# Headstage_withFPGA.net
KiCad netlist of a schematic drawn in Altium Designer
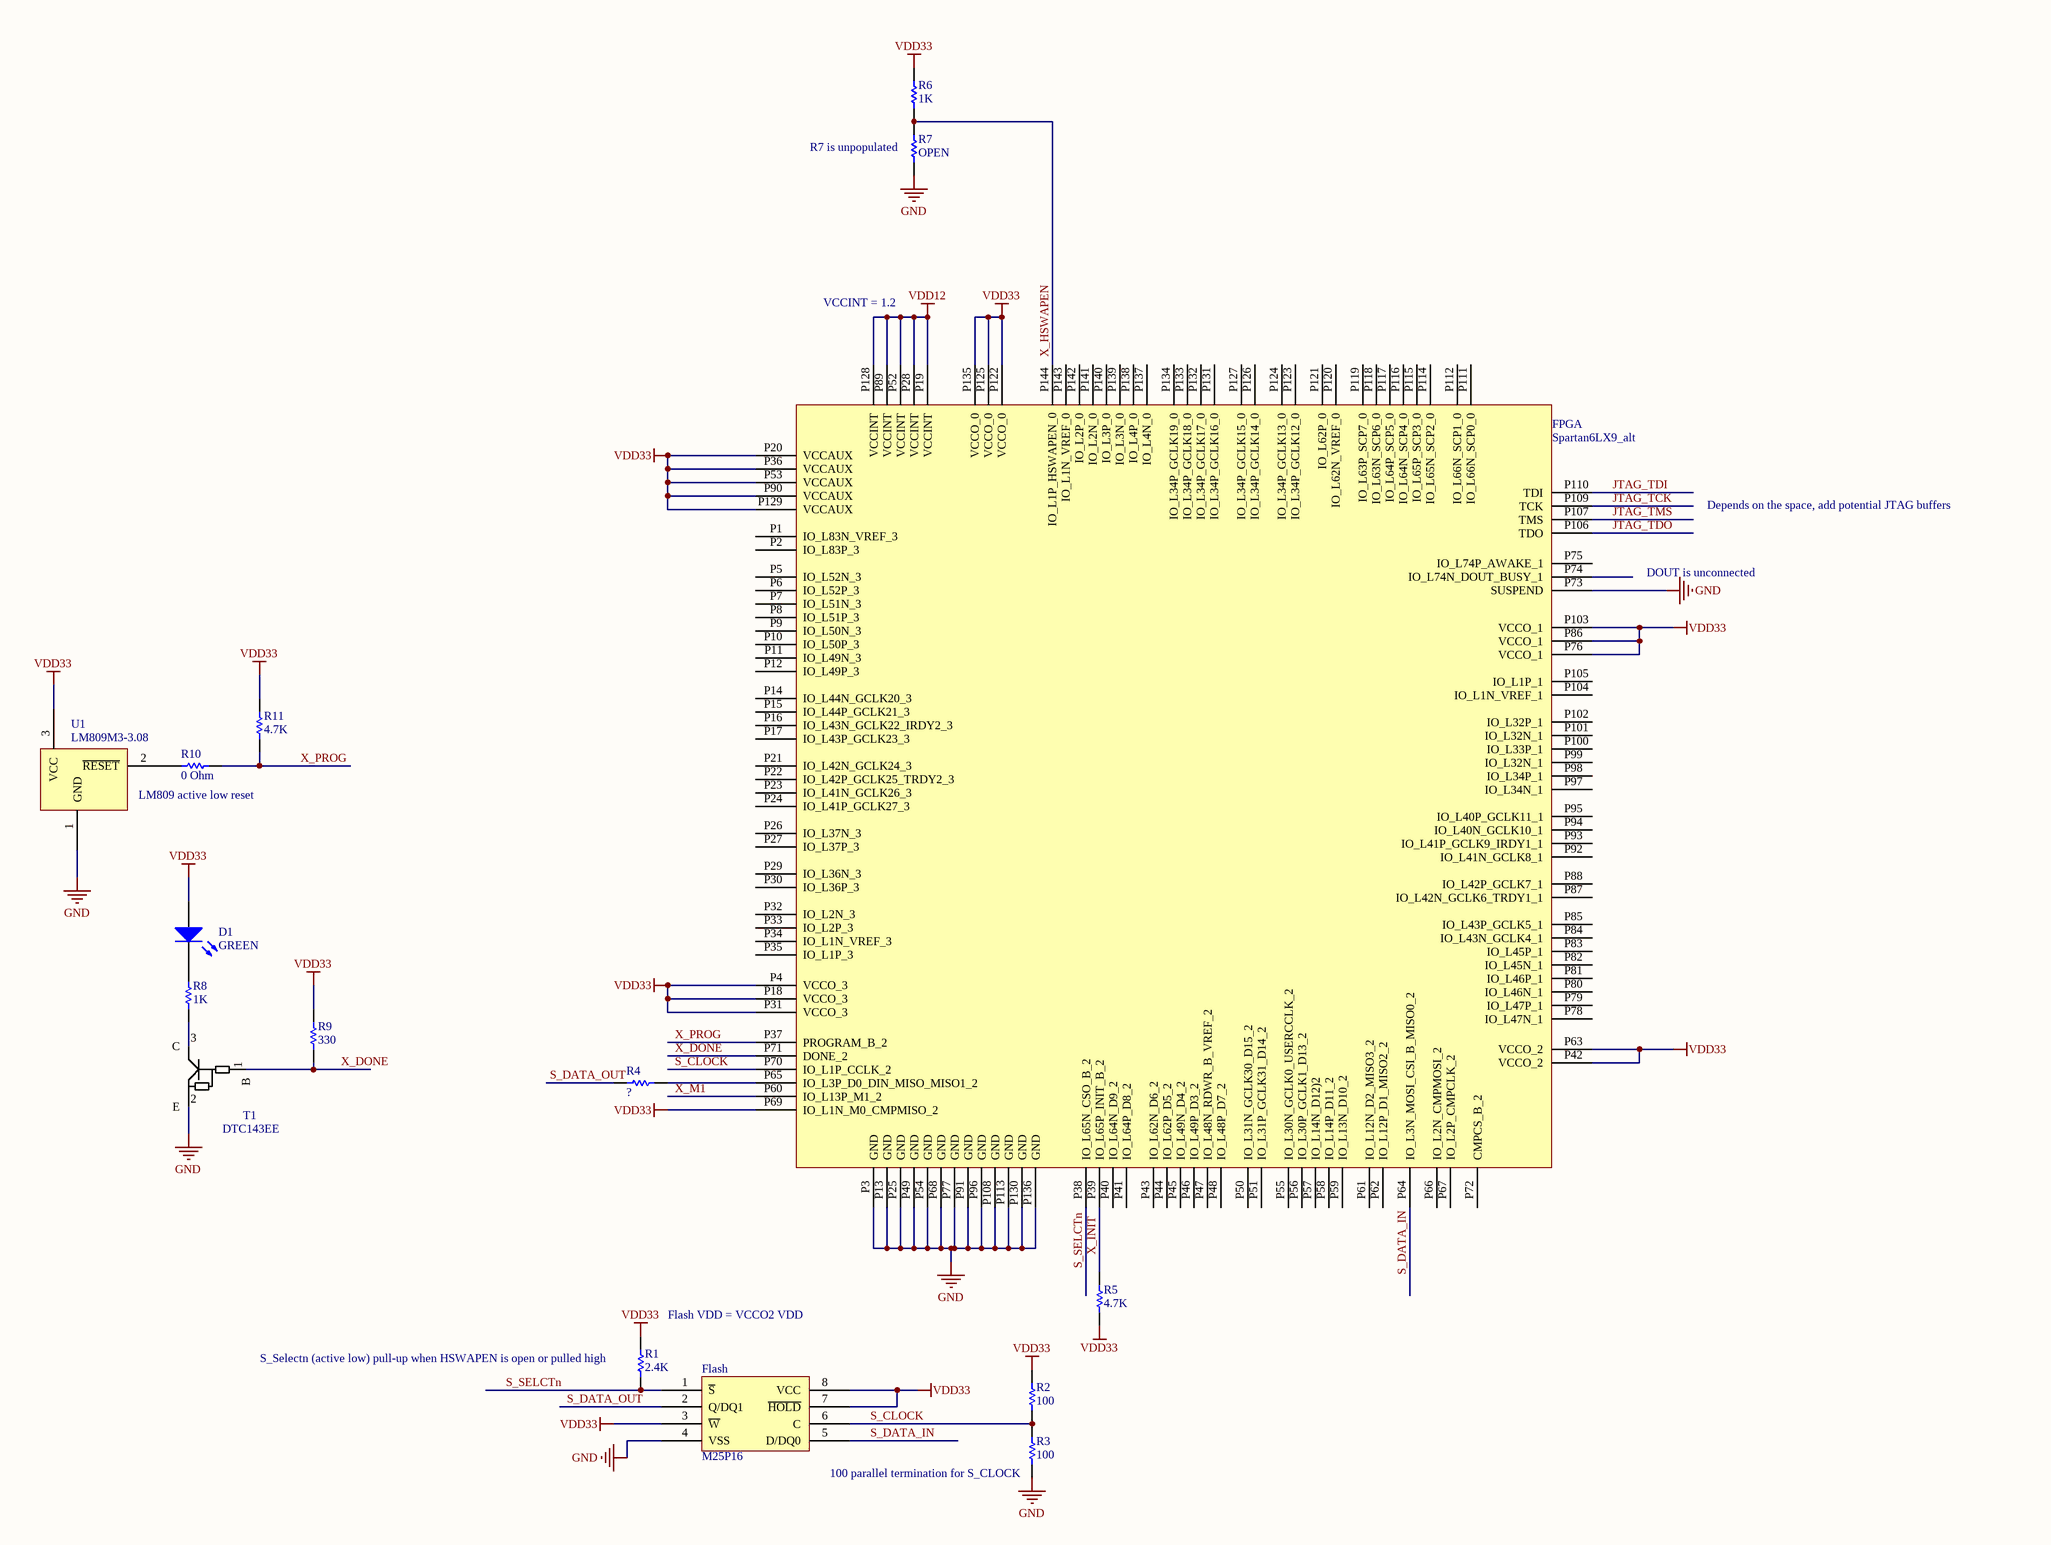
[diagram p0: Headstage_withFPGA.SchDoc]

(export (version "E")
  (design (tool "Eeschema 10.0.6"))
  (components
    (comp (ref "D1")
      (value "GREEN")
      (description "Typical BLUE SiC LED")
      (fields (field (name "PUBLISHER") "Altium Limited"))
      (libsource (lib "Miscellaneous Devices") (part "LED3"))
    )
    (comp (ref "Flash") (value "M25P16") (libsource (lib "Jack_SCH_Lib1") (part "M25P16")))
    (comp (ref "FPGA") (value "Spartan6LX9_alt") (libsource (lib "Jack_SCH_Lib1") (part "Spartan6LX9_alt")))
    (comp (ref "R1")
      (value "2.4K")
      (footprint "AXIAL-0.3")
      (description "Resistor")
      (fields (field (name "Comment") "Res1") (field (name "PUBLISHER") "Altium Limited"))
      (libsource (lib "Miscellaneous Devices") (part "Res1"))
    )
    (comp (ref "R2")
      (value "100")
      (footprint "AXIAL-0.3")
      (description "Resistor")
      (fields (field (name "Comment") "Res1") (field (name "PUBLISHER") "Altium Limited"))
      (libsource (lib "Miscellaneous Devices") (part "Res1"))
    )
    (comp (ref "R3")
      (value "100")
      (footprint "AXIAL-0.3")
      (description "Resistor")
      (fields (field (name "Comment") "Res1") (field (name "PUBLISHER") "Altium Limited"))
      (libsource (lib "Miscellaneous Devices") (part "Res1"))
    )
    (comp (ref "R4")
      (value "?")
      (footprint "AXIAL-0.3")
      (description "Resistor")
      (fields (field (name "Comment") "Res1") (field (name "PUBLISHER") "Altium Limited"))
      (libsource (lib "Miscellaneous Devices") (part "Res1"))
    )
    (comp (ref "R5")
      (value "4.7K")
      (footprint "AXIAL-0.3")
      (description "Resistor")
      (fields (field (name "Comment") "Res1") (field (name "PUBLISHER") "Altium Limited"))
      (libsource (lib "Miscellaneous Devices") (part "Res1"))
    )
    (comp (ref "R6")
      (value "1K")
      (footprint "AXIAL-0.3")
      (description "Resistor")
      (fields (field (name "Comment") "Res1") (field (name "PUBLISHER") "Altium Limited"))
      (libsource (lib "Miscellaneous Devices") (part "Res1"))
    )
    (comp (ref "R7")
      (value "OPEN")
      (footprint "AXIAL-0.3")
      (description "Resistor")
      (fields (field (name "Comment") "Res1") (field (name "PUBLISHER") "Altium Limited"))
      (libsource (lib "Miscellaneous Devices") (part "Res1"))
    )
    (comp (ref "R8")
      (value "1K")
      (footprint "AXIAL-0.3")
      (description "Resistor")
      (fields (field (name "Comment") "Res1") (field (name "PUBLISHER") "Altium Limited"))
      (libsource (lib "Miscellaneous Devices") (part "Res1"))
    )
    (comp (ref "R9")
      (value "330")
      (footprint "AXIAL-0.3")
      (description "Resistor")
      (fields (field (name "Comment") "Res1") (field (name "PUBLISHER") "Altium Limited"))
      (libsource (lib "Miscellaneous Devices") (part "Res1"))
    )
    (comp (ref "R10")
      (value "0 Ohm")
      (footprint "AXIAL-0.3")
      (description "Resistor")
      (fields (field (name "Comment") "Res1") (field (name "PUBLISHER") "Altium Limited"))
      (libsource (lib "Miscellaneous Devices") (part "Res1"))
    )
    (comp (ref "R11")
      (value "4.7K")
      (footprint "AXIAL-0.3")
      (description "Resistor")
      (fields (field (name "Comment") "Res1") (field (name "PUBLISHER") "Altium Limited"))
      (libsource (lib "Miscellaneous Devices") (part "Res1"))
    )
    (comp (ref "T1") (value "DTC143EE") (libsource (lib "Jack_SCH_Lib1") (part "DTC143EE")))
    (comp (ref "U1") (value "LM809M3-3.08") (libsource (lib "Jack_SCH_Lib1") (part "LM809M3-3.08")))
  )
  (nets
    (net (code "1") (name "/JTAG_TCK") (class "Default")
      (node (ref "FPGA") (pin "P109") (pinfunction "TCK_P109") (pintype "passive"))
    )
    (net (code "2") (name "/JTAG_TDI") (class "Default")
      (node (ref "FPGA") (pin "P110") (pinfunction "TDI_P110") (pintype "passive"))
    )
    (net (code "3") (name "/JTAG_TDO") (class "Default")
      (node (ref "FPGA") (pin "P106") (pinfunction "TDO_P106") (pintype "passive"))
    )
    (net (code "4") (name "/JTAG_TMS") (class "Default")
      (node (ref "FPGA") (pin "P107") (pinfunction "TMS_P107") (pintype "passive"))
    )
    (net (code "5") (name "/S_CLOCK") (class "Default")
      (node (ref "FPGA") (pin "P70") (pinfunction "IO_L1P_CCLK_2_P70") (pintype "passive"))
      (node (ref "Flash") (pin "6") (pinfunction "C_6") (pintype "passive"))
      (node (ref "R2") (pin "1") (pinfunction "1_1") (pintype "passive"))
      (node (ref "R3") (pin "2") (pinfunction "2_2") (pintype "passive"))
    )
    (net (code "6") (name "/S_DATA_IN") (class "Default")
      (node (ref "FPGA") (pin "P64") (pinfunction "IO_L3N_MOSI_CSI_B_MISO0_2_P64") (pintype "passive"))
      (node (ref "Flash") (pin "5") (pinfunction "D/DQ0_5") (pintype "passive"))
    )
    (net (code "7") (name "/S_DATA_OUT") (class "Default")
      (node (ref "Flash") (pin "2") (pinfunction "Q/DQ1_2") (pintype "passive"))
      (node (ref "R4") (pin "2") (pinfunction "2_2") (pintype "passive"))
    )
    (net (code "8") (name "/S_SELCTn") (class "Default")
      (node (ref "FPGA") (pin "P38") (pinfunction "IO_L65N_CSO_B_2_P38") (pintype "passive"))
      (node (ref "Flash") (pin "1") (pinfunction "~{S}_1") (pintype "passive"))
      (node (ref "R1") (pin "1") (pinfunction "1_1") (pintype "passive"))
    )
    (net (code "9") (name "/X_DONE") (class "Default")
      (node (ref "FPGA") (pin "P71") (pinfunction "DONE_2_P71") (pintype "passive"))
      (node (ref "R9") (pin "1") (pinfunction "1_1") (pintype "passive"))
      (node (ref "T1") (pin "1") (pinfunction "B_1") (pintype "passive"))
    )
    (net (code "10") (name "/X_HSWAPEN") (class "Default")
      (node (ref "FPGA") (pin "P144") (pinfunction "IO_L1P_HSWAPEN_0_P144") (pintype "passive"))
      (node (ref "R6") (pin "1") (pinfunction "1_1") (pintype "passive"))
      (node (ref "R7") (pin "2") (pinfunction "2_2") (pintype "passive"))
    )
    (net (code "11") (name "/X_INIT") (class "Default")
      (node (ref "FPGA") (pin "P39") (pinfunction "IO_L65P_INIT_B_2_P39") (pintype "passive"))
      (node (ref "R5") (pin "2") (pinfunction "2_2") (pintype "passive"))
    )
    (net (code "12") (name "/X_M1") (class "Default")
      (node (ref "FPGA") (pin "P60") (pinfunction "IO_L13P_M1_2_P60") (pintype "passive"))
    )
    (net (code "13") (name "/X_PROG") (class "Default")
      (node (ref "FPGA") (pin "P37") (pinfunction "PROGRAM_B_2_P37") (pintype "passive"))
      (node (ref "R10") (pin "1") (pinfunction "1_1") (pintype "passive"))
      (node (ref "R11") (pin "2") (pinfunction "2_2") (pintype "passive"))
    )
    (net (code "14") (name "GND") (class "Default")
      (node (ref "FPGA") (pin "P108") (pinfunction "GND_P108") (pintype "passive"))
      (node (ref "FPGA") (pin "P113") (pinfunction "GND_P113") (pintype "passive"))
      (node (ref "FPGA") (pin "P13") (pinfunction "GND_P13") (pintype "passive"))
      (node (ref "FPGA") (pin "P130") (pinfunction "GND_P130") (pintype "passive"))
      (node (ref "FPGA") (pin "P136") (pinfunction "GND_P136") (pintype "passive"))
      (node (ref "FPGA") (pin "P25") (pinfunction "GND_P25") (pintype "passive"))
      (node (ref "FPGA") (pin "P3") (pinfunction "GND_P3") (pintype "passive"))
      (node (ref "FPGA") (pin "P49") (pinfunction "GND_P49") (pintype "passive"))
      (node (ref "FPGA") (pin "P54") (pinfunction "GND_P54") (pintype "passive"))
      (node (ref "FPGA") (pin "P68") (pinfunction "GND_P68") (pintype "passive"))
      (node (ref "FPGA") (pin "P73") (pinfunction "SUSPEND_P73") (pintype "passive"))
      (node (ref "FPGA") (pin "P77") (pinfunction "GND_P77") (pintype "passive"))
      (node (ref "FPGA") (pin "P91") (pinfunction "GND_P91") (pintype "passive"))
      (node (ref "FPGA") (pin "P96") (pinfunction "GND_P96") (pintype "passive"))
      (node (ref "Flash") (pin "4") (pinfunction "VSS_4") (pintype "passive"))
      (node (ref "R3") (pin "1") (pinfunction "1_1") (pintype "passive"))
      (node (ref "R7") (pin "1") (pinfunction "1_1") (pintype "passive"))
      (node (ref "T1") (pin "2") (pinfunction "E_2") (pintype "passive"))
      (node (ref "U1") (pin "1") (pinfunction "GND_1") (pintype "passive"))
    )
    (net (code "15") (name "Net-(D1-K)") (class "Default")
      (node (ref "D1") (pin "2") (pinfunction "K_2") (pintype "passive"))
      (node (ref "R8") (pin "2") (pinfunction "2_2") (pintype "passive"))
    )
    (net (code "16") (name "Net-(FPGA-IO_L3P_D0_DIN_MISO_MISO1_2)") (class "Default")
      (node (ref "FPGA") (pin "P65") (pinfunction "IO_L3P_D0_DIN_MISO_MISO1_2_P65") (pintype "passive"))
      (node (ref "R4") (pin "1") (pinfunction "1_1") (pintype "passive"))
    )
    (net (code "17") (name "Net-(T1-C)") (class "Default")
      (node (ref "R8") (pin "1") (pinfunction "1_1") (pintype "passive"))
      (node (ref "T1") (pin "3") (pinfunction "C_3") (pintype "passive"))
    )
    (net (code "18") (name "Net-(U1-~{RESET})") (class "Default")
      (node (ref "R10") (pin "2") (pinfunction "2_2") (pintype "passive"))
      (node (ref "U1") (pin "2") (pinfunction "~{RESET}_2") (pintype "passive"))
    )
    (net (code "19") (name "VDD12") (class "Default")
      (node (ref "FPGA") (pin "P128") (pinfunction "VCCINT_P128") (pintype "passive"))
      (node (ref "FPGA") (pin "P19") (pinfunction "VCCINT_P19") (pintype "passive"))
      (node (ref "FPGA") (pin "P28") (pinfunction "VCCINT_P28") (pintype "passive"))
      (node (ref "FPGA") (pin "P52") (pinfunction "VCCINT_P52") (pintype "passive"))
      (node (ref "FPGA") (pin "P89") (pinfunction "VCCINT_P89") (pintype "passive"))
    )
    (net (code "20") (name "VDD33") (class "Default")
      (node (ref "D1") (pin "1") (pinfunction "A_1") (pintype "passive"))
      (node (ref "FPGA") (pin "P103") (pinfunction "VCCO_1_P103") (pintype "passive"))
      (node (ref "FPGA") (pin "P122") (pinfunction "VCCO_0_P122") (pintype "passive"))
      (node (ref "FPGA") (pin "P125") (pinfunction "VCCO_0_P125") (pintype "passive"))
      (node (ref "FPGA") (pin "P129") (pinfunction "VCCAUX_P129") (pintype "passive"))
      (node (ref "FPGA") (pin "P135") (pinfunction "VCCO_0_P135") (pintype "passive"))
      (node (ref "FPGA") (pin "P18") (pinfunction "VCCO_3_P18") (pintype "passive"))
      (node (ref "FPGA") (pin "P20") (pinfunction "VCCAUX_P20") (pintype "passive"))
      (node (ref "FPGA") (pin "P31") (pinfunction "VCCO_3_P31") (pintype "passive"))
      (node (ref "FPGA") (pin "P36") (pinfunction "VCCAUX_P36") (pintype "passive"))
      (node (ref "FPGA") (pin "P4") (pinfunction "VCCO_3_P4") (pintype "passive"))
      (node (ref "FPGA") (pin "P42") (pinfunction "VCCO_2_P42") (pintype "passive"))
      (node (ref "FPGA") (pin "P53") (pinfunction "VCCAUX_P53") (pintype "passive"))
      (node (ref "FPGA") (pin "P63") (pinfunction "VCCO_2_P63") (pintype "passive"))
      (node (ref "FPGA") (pin "P69") (pinfunction "IO_L1N_M0_CMPMISO_2_P69") (pintype "passive"))
      (node (ref "FPGA") (pin "P76") (pinfunction "VCCO_1_P76") (pintype "passive"))
      (node (ref "FPGA") (pin "P86") (pinfunction "VCCO_1_P86") (pintype "passive"))
      (node (ref "FPGA") (pin "P90") (pinfunction "VCCAUX_P90") (pintype "passive"))
      (node (ref "Flash") (pin "3") (pinfunction "~{W}_3") (pintype "passive"))
      (node (ref "Flash") (pin "7") (pinfunction "~{HOLD}_7") (pintype "passive"))
      (node (ref "Flash") (pin "8") (pinfunction "VCC_8") (pintype "passive"))
      (node (ref "R1") (pin "2") (pinfunction "2_2") (pintype "passive"))
      (node (ref "R11") (pin "1") (pinfunction "1_1") (pintype "passive"))
      (node (ref "R2") (pin "2") (pinfunction "2_2") (pintype "passive"))
      (node (ref "R5") (pin "1") (pinfunction "1_1") (pintype "passive"))
      (node (ref "R6") (pin "2") (pinfunction "2_2") (pintype "passive"))
      (node (ref "R9") (pin "2") (pinfunction "2_2") (pintype "passive"))
      (node (ref "U1") (pin "3") (pinfunction "VCC_3") (pintype "passive"))
    )
    (net (code "21") (name "unconnected-(FPGA-CMPCS_B_2-PadP72)") (class "Default")
      (node (ref "FPGA") (pin "P72") (pinfunction "CMPCS_B_2_P72") (pintype "passive"))
    )
    (net (code "22") (name "unconnected-(FPGA-IO_L1N_VREF_0-PadP143)") (class "Default")
      (node (ref "FPGA") (pin "P143") (pinfunction "IO_L1N_VREF_0_P143") (pintype "passive"))
    )
    (net (code "23") (name "unconnected-(FPGA-IO_L1N_VREF_1-PadP104)") (class "Default")
      (node (ref "FPGA") (pin "P104") (pinfunction "IO_L1N_VREF_1_P104") (pintype "passive"))
    )
    (net (code "24") (name "unconnected-(FPGA-IO_L1N_VREF_3-PadP34)") (class "Default")
      (node (ref "FPGA") (pin "P34") (pinfunction "IO_L1N_VREF_3_P34") (pintype "passive"))
    )
    (net (code "25") (name "unconnected-(FPGA-IO_L1P_1-PadP105)") (class "Default")
      (node (ref "FPGA") (pin "P105") (pinfunction "IO_L1P_1_P105") (pintype "passive"))
    )
    (net (code "26") (name "unconnected-(FPGA-IO_L1P_3-PadP35)") (class "Default")
      (node (ref "FPGA") (pin "P35") (pinfunction "IO_L1P_3_P35") (pintype "passive"))
    )
    (net (code "27") (name "unconnected-(FPGA-IO_L2N_0-PadP141)") (class "Default")
      (node (ref "FPGA") (pin "P141") (pinfunction "IO_L2N_0_P141") (pintype "passive"))
    )
    (net (code "28") (name "unconnected-(FPGA-IO_L2N_3-PadP32)") (class "Default")
      (node (ref "FPGA") (pin "P32") (pinfunction "IO_L2N_3_P32") (pintype "passive"))
    )
    (net (code "29") (name "unconnected-(FPGA-IO_L2N_CMPMOSI_2-PadP66)") (class "Default")
      (node (ref "FPGA") (pin "P66") (pinfunction "IO_L2N_CMPMOSI_2_P66") (pintype "passive"))
    )
    (net (code "30") (name "unconnected-(FPGA-IO_L2P_0-PadP142)") (class "Default")
      (node (ref "FPGA") (pin "P142") (pinfunction "IO_L2P_0_P142") (pintype "passive"))
    )
    (net (code "31") (name "unconnected-(FPGA-IO_L2P_3-PadP33)") (class "Default")
      (node (ref "FPGA") (pin "P33") (pinfunction "IO_L2P_3_P33") (pintype "passive"))
    )
    (net (code "32") (name "unconnected-(FPGA-IO_L2P_CMPCLK_2-PadP67)") (class "Default")
      (node (ref "FPGA") (pin "P67") (pinfunction "IO_L2P_CMPCLK_2_P67") (pintype "passive"))
    )
    (net (code "33") (name "unconnected-(FPGA-IO_L3N_0-PadP139)") (class "Default")
      (node (ref "FPGA") (pin "P139") (pinfunction "IO_L3N_0_P139") (pintype "passive"))
    )
    (net (code "34") (name "unconnected-(FPGA-IO_L3P_0-PadP140)") (class "Default")
      (node (ref "FPGA") (pin "P140") (pinfunction "IO_L3P_0_P140") (pintype "passive"))
    )
    (net (code "35") (name "unconnected-(FPGA-IO_L4N_0-PadP137)") (class "Default")
      (node (ref "FPGA") (pin "P137") (pinfunction "IO_L4N_0_P137") (pintype "passive"))
    )
    (net (code "36") (name "unconnected-(FPGA-IO_L4P_0-PadP138)") (class "Default")
      (node (ref "FPGA") (pin "P138") (pinfunction "IO_L4P_0_P138") (pintype "passive"))
    )
    (net (code "37") (name "unconnected-(FPGA-IO_L12N_D2_MISO3_2-PadP61)") (class "Default")
      (node (ref "FPGA") (pin "P61") (pinfunction "IO_L12N_D2_MISO3_2_P61") (pintype "passive"))
    )
    (net (code "38") (name "unconnected-(FPGA-IO_L12P_D1_MISO2_2-PadP62)") (class "Default")
      (node (ref "FPGA") (pin "P62") (pinfunction "IO_L12P_D1_MISO2_2_P62") (pintype "passive"))
    )
    (net (code "39") (name "unconnected-(FPGA-IO_L13N_D10_2-PadP59)") (class "Default")
      (node (ref "FPGA") (pin "P59") (pinfunction "IO_L13N_D10_2_P59") (pintype "passive"))
    )
    (net (code "40") (name "unconnected-(FPGA-IO_L14N_D12)2-PadP57)") (class "Default")
      (node (ref "FPGA") (pin "P57") (pinfunction "IO_L14N_D12)2_P57") (pintype "passive"))
    )
    (net (code "41") (name "unconnected-(FPGA-IO_L14P_D11_2-PadP58)") (class "Default")
      (node (ref "FPGA") (pin "P58") (pinfunction "IO_L14P_D11_2_P58") (pintype "passive"))
    )
    (net (code "42") (name "unconnected-(FPGA-IO_L30N_GCLK0_USERCCLK_2-PadP55)") (class "Default")
      (node (ref "FPGA") (pin "P55") (pinfunction "IO_L30N_GCLK0_USERCCLK_2_P55") (pintype "passive"))
    )
    (net (code "43") (name "unconnected-(FPGA-IO_L30P_GCLK1_D13_2-PadP56)") (class "Default")
      (node (ref "FPGA") (pin "P56") (pinfunction "IO_L30P_GCLK1_D13_2_P56") (pintype "passive"))
    )
    (net (code "44") (name "unconnected-(FPGA-IO_L31N_GCLK30_D15_2-PadP50)") (class "Default")
      (node (ref "FPGA") (pin "P50") (pinfunction "IO_L31N_GCLK30_D15_2_P50") (pintype "passive"))
    )
    (net (code "45") (name "unconnected-(FPGA-IO_L31P_GCLK31_D14_2-PadP51)") (class "Default")
      (node (ref "FPGA") (pin "P51") (pinfunction "IO_L31P_GCLK31_D14_2_P51") (pintype "passive"))
    )
    (net (code "46") (name "unconnected-(FPGA-IO_L32N_1-PadP99)") (class "Default")
      (node (ref "FPGA") (pin "P99") (pinfunction "IO_L32N_1_P99") (pintype "passive"))
    )
    (net (code "47") (name "unconnected-(FPGA-IO_L32N_1-PadP101)") (class "Default")
      (node (ref "FPGA") (pin "P101") (pinfunction "IO_L32N_1_P101") (pintype "passive"))
    )
    (net (code "48") (name "unconnected-(FPGA-IO_L32P_1-PadP102)") (class "Default")
      (node (ref "FPGA") (pin "P102") (pinfunction "IO_L32P_1_P102") (pintype "passive"))
    )
    (net (code "49") (name "unconnected-(FPGA-IO_L33P_1-PadP100)") (class "Default")
      (node (ref "FPGA") (pin "P100") (pinfunction "IO_L33P_1_P100") (pintype "passive"))
    )
    (net (code "50") (name "unconnected-(FPGA-IO_L34N_1-PadP97)") (class "Default")
      (node (ref "FPGA") (pin "P97") (pinfunction "IO_L34N_1_P97") (pintype "passive"))
    )
    (net (code "51") (name "unconnected-(FPGA-IO_L34P_1-PadP98)") (class "Default")
      (node (ref "FPGA") (pin "P98") (pinfunction "IO_L34P_1_P98") (pintype "passive"))
    )
    (net (code "52") (name "unconnected-(FPGA-IO_L34P_GCLK12_0-PadP123)") (class "Default")
      (node (ref "FPGA") (pin "P123") (pinfunction "IO_L34P_GCLK12_0_P123") (pintype "passive"))
    )
    (net (code "53") (name "unconnected-(FPGA-IO_L34P_GCLK13_0-PadP124)") (class "Default")
      (node (ref "FPGA") (pin "P124") (pinfunction "IO_L34P_GCLK13_0_P124") (pintype "passive"))
    )
    (net (code "54") (name "unconnected-(FPGA-IO_L34P_GCLK14_0-PadP126)") (class "Default")
      (node (ref "FPGA") (pin "P126") (pinfunction "IO_L34P_GCLK14_0_P126") (pintype "passive"))
    )
    (net (code "55") (name "unconnected-(FPGA-IO_L34P_GCLK15_0-PadP127)") (class "Default")
      (node (ref "FPGA") (pin "P127") (pinfunction "IO_L34P_GCLK15_0_P127") (pintype "passive"))
    )
    (net (code "56") (name "unconnected-(FPGA-IO_L34P_GCLK16_0-PadP131)") (class "Default")
      (node (ref "FPGA") (pin "P131") (pinfunction "IO_L34P_GCLK16_0_P131") (pintype "passive"))
    )
    (net (code "57") (name "unconnected-(FPGA-IO_L34P_GCLK17_0-PadP132)") (class "Default")
      (node (ref "FPGA") (pin "P132") (pinfunction "IO_L34P_GCLK17_0_P132") (pintype "passive"))
    )
    (net (code "58") (name "unconnected-(FPGA-IO_L34P_GCLK18_0-PadP133)") (class "Default")
      (node (ref "FPGA") (pin "P133") (pinfunction "IO_L34P_GCLK18_0_P133") (pintype "passive"))
    )
    (net (code "59") (name "unconnected-(FPGA-IO_L34P_GCLK19_0-PadP134)") (class "Default")
      (node (ref "FPGA") (pin "P134") (pinfunction "IO_L34P_GCLK19_0_P134") (pintype "passive"))
    )
    (net (code "60") (name "unconnected-(FPGA-IO_L36N_3-PadP29)") (class "Default")
      (node (ref "FPGA") (pin "P29") (pinfunction "IO_L36N_3_P29") (pintype "passive"))
    )
    (net (code "61") (name "unconnected-(FPGA-IO_L36P_3-PadP30)") (class "Default")
      (node (ref "FPGA") (pin "P30") (pinfunction "IO_L36P_3_P30") (pintype "passive"))
    )
    (net (code "62") (name "unconnected-(FPGA-IO_L37N_3-PadP26)") (class "Default")
      (node (ref "FPGA") (pin "P26") (pinfunction "IO_L37N_3_P26") (pintype "passive"))
    )
    (net (code "63") (name "unconnected-(FPGA-IO_L37P_3-PadP27)") (class "Default")
      (node (ref "FPGA") (pin "P27") (pinfunction "IO_L37P_3_P27") (pintype "passive"))
    )
    (net (code "64") (name "unconnected-(FPGA-IO_L40N_GCLK10_1-PadP94)") (class "Default")
      (node (ref "FPGA") (pin "P94") (pinfunction "IO_L40N_GCLK10_1_P94") (pintype "passive"))
    )
    (net (code "65") (name "unconnected-(FPGA-IO_L40P_GCLK11_1-PadP95)") (class "Default")
      (node (ref "FPGA") (pin "P95") (pinfunction "IO_L40P_GCLK11_1_P95") (pintype "passive"))
    )
    (net (code "66") (name "unconnected-(FPGA-IO_L41N_GCLK8_1-PadP92)") (class "Default")
      (node (ref "FPGA") (pin "P92") (pinfunction "IO_L41N_GCLK8_1_P92") (pintype "passive"))
    )
    (net (code "67") (name "unconnected-(FPGA-IO_L41N_GCLK26_3-PadP23)") (class "Default")
      (node (ref "FPGA") (pin "P23") (pinfunction "IO_L41N_GCLK26_3_P23") (pintype "passive"))
    )
    (net (code "68") (name "unconnected-(FPGA-IO_L41P_GCLK9_IRDY1_1-PadP93)") (class "Default")
      (node (ref "FPGA") (pin "P93") (pinfunction "IO_L41P_GCLK9_IRDY1_1_P93") (pintype "passive"))
    )
    (net (code "69") (name "unconnected-(FPGA-IO_L41P_GCLK27_3-PadP24)") (class "Default")
      (node (ref "FPGA") (pin "P24") (pinfunction "IO_L41P_GCLK27_3_P24") (pintype "passive"))
    )
    (net (code "70") (name "unconnected-(FPGA-IO_L42N_GCLK6_TRDY1_1-PadP87)") (class "Default")
      (node (ref "FPGA") (pin "P87") (pinfunction "IO_L42N_GCLK6_TRDY1_1_P87") (pintype "passive"))
    )
    (net (code "71") (name "unconnected-(FPGA-IO_L42N_GCLK24_3-PadP21)") (class "Default")
      (node (ref "FPGA") (pin "P21") (pinfunction "IO_L42N_GCLK24_3_P21") (pintype "passive"))
    )
    (net (code "72") (name "unconnected-(FPGA-IO_L42P_GCLK7_1-PadP88)") (class "Default")
      (node (ref "FPGA") (pin "P88") (pinfunction "IO_L42P_GCLK7_1_P88") (pintype "passive"))
    )
    (net (code "73") (name "unconnected-(FPGA-IO_L42P_GCLK25_TRDY2_3-PadP22)") (class "Default")
      (node (ref "FPGA") (pin "P22") (pinfunction "IO_L42P_GCLK25_TRDY2_3_P22") (pintype "passive"))
    )
    (net (code "74") (name "unconnected-(FPGA-IO_L43N_GCLK4_1-PadP84)") (class "Default")
      (node (ref "FPGA") (pin "P84") (pinfunction "IO_L43N_GCLK4_1_P84") (pintype "passive"))
    )
    (net (code "75") (name "unconnected-(FPGA-IO_L43N_GCLK22_IRDY2_3-PadP16)") (class "Default")
      (node (ref "FPGA") (pin "P16") (pinfunction "IO_L43N_GCLK22_IRDY2_3_P16") (pintype "passive"))
    )
    (net (code "76") (name "unconnected-(FPGA-IO_L43P_GCLK5_1-PadP85)") (class "Default")
      (node (ref "FPGA") (pin "P85") (pinfunction "IO_L43P_GCLK5_1_P85") (pintype "passive"))
    )
    (net (code "77") (name "unconnected-(FPGA-IO_L43P_GCLK23_3-PadP17)") (class "Default")
      (node (ref "FPGA") (pin "P17") (pinfunction "IO_L43P_GCLK23_3_P17") (pintype "passive"))
    )
    (net (code "78") (name "unconnected-(FPGA-IO_L44N_GCLK20_3-PadP14)") (class "Default")
      (node (ref "FPGA") (pin "P14") (pinfunction "IO_L44N_GCLK20_3_P14") (pintype "passive"))
    )
    (net (code "79") (name "unconnected-(FPGA-IO_L44P_GCLK21_3-PadP15)") (class "Default")
      (node (ref "FPGA") (pin "P15") (pinfunction "IO_L44P_GCLK21_3_P15") (pintype "passive"))
    )
    (net (code "80") (name "unconnected-(FPGA-IO_L45N_1-PadP82)") (class "Default")
      (node (ref "FPGA") (pin "P82") (pinfunction "IO_L45N_1_P82") (pintype "passive"))
    )
    (net (code "81") (name "unconnected-(FPGA-IO_L45P_1-PadP83)") (class "Default")
      (node (ref "FPGA") (pin "P83") (pinfunction "IO_L45P_1_P83") (pintype "passive"))
    )
    (net (code "82") (name "unconnected-(FPGA-IO_L46N_1-PadP80)") (class "Default")
      (node (ref "FPGA") (pin "P80") (pinfunction "IO_L46N_1_P80") (pintype "passive"))
    )
    (net (code "83") (name "unconnected-(FPGA-IO_L46P_1-PadP81)") (class "Default")
      (node (ref "FPGA") (pin "P81") (pinfunction "IO_L46P_1_P81") (pintype "passive"))
    )
    (net (code "84") (name "unconnected-(FPGA-IO_L47N_1-PadP78)") (class "Default")
      (node (ref "FPGA") (pin "P78") (pinfunction "IO_L47N_1_P78") (pintype "passive"))
    )
    (net (code "85") (name "unconnected-(FPGA-IO_L47P_1-PadP79)") (class "Default")
      (node (ref "FPGA") (pin "P79") (pinfunction "IO_L47P_1_P79") (pintype "passive"))
    )
    (net (code "86") (name "unconnected-(FPGA-IO_L48N_RDWR_B_VREF_2-PadP47)") (class "Default")
      (node (ref "FPGA") (pin "P47") (pinfunction "IO_L48N_RDWR_B_VREF_2_P47") (pintype "passive"))
    )
    (net (code "87") (name "unconnected-(FPGA-IO_L48P_D7_2-PadP48)") (class "Default")
      (node (ref "FPGA") (pin "P48") (pinfunction "IO_L48P_D7_2_P48") (pintype "passive"))
    )
    (net (code "88") (name "unconnected-(FPGA-IO_L49N_3-PadP11)") (class "Default")
      (node (ref "FPGA") (pin "P11") (pinfunction "IO_L49N_3_P11") (pintype "passive"))
    )
    (net (code "89") (name "unconnected-(FPGA-IO_L49N_D4_2-PadP45)") (class "Default")
      (node (ref "FPGA") (pin "P45") (pinfunction "IO_L49N_D4_2_P45") (pintype "passive"))
    )
    (net (code "90") (name "unconnected-(FPGA-IO_L49P_3-PadP12)") (class "Default")
      (node (ref "FPGA") (pin "P12") (pinfunction "IO_L49P_3_P12") (pintype "passive"))
    )
    (net (code "91") (name "unconnected-(FPGA-IO_L49P_D3_2-PadP46)") (class "Default")
      (node (ref "FPGA") (pin "P46") (pinfunction "IO_L49P_D3_2_P46") (pintype "passive"))
    )
    (net (code "92") (name "unconnected-(FPGA-IO_L50N_3-PadP9)") (class "Default")
      (node (ref "FPGA") (pin "P9") (pinfunction "IO_L50N_3_P9") (pintype "passive"))
    )
    (net (code "93") (name "unconnected-(FPGA-IO_L50P_3-PadP10)") (class "Default")
      (node (ref "FPGA") (pin "P10") (pinfunction "IO_L50P_3_P10") (pintype "passive"))
    )
    (net (code "94") (name "unconnected-(FPGA-IO_L51N_3-PadP7)") (class "Default")
      (node (ref "FPGA") (pin "P7") (pinfunction "IO_L51N_3_P7") (pintype "passive"))
    )
    (net (code "95") (name "unconnected-(FPGA-IO_L51P_3-PadP8)") (class "Default")
      (node (ref "FPGA") (pin "P8") (pinfunction "IO_L51P_3_P8") (pintype "passive"))
    )
    (net (code "96") (name "unconnected-(FPGA-IO_L52N_3-PadP5)") (class "Default")
      (node (ref "FPGA") (pin "P5") (pinfunction "IO_L52N_3_P5") (pintype "passive"))
    )
    (net (code "97") (name "unconnected-(FPGA-IO_L52P_3-PadP6)") (class "Default")
      (node (ref "FPGA") (pin "P6") (pinfunction "IO_L52P_3_P6") (pintype "passive"))
    )
    (net (code "98") (name "unconnected-(FPGA-IO_L62N_D6_2-PadP43)") (class "Default")
      (node (ref "FPGA") (pin "P43") (pinfunction "IO_L62N_D6_2_P43") (pintype "passive"))
    )
    (net (code "99") (name "unconnected-(FPGA-IO_L62N_VREF_0-PadP120)") (class "Default")
      (node (ref "FPGA") (pin "P120") (pinfunction "IO_L62N_VREF_0_P120") (pintype "passive"))
    )
    (net (code "100") (name "unconnected-(FPGA-IO_L62P_0-PadP121)") (class "Default")
      (node (ref "FPGA") (pin "P121") (pinfunction "IO_L62P_0_P121") (pintype "passive"))
    )
    (net (code "101") (name "unconnected-(FPGA-IO_L62P_D5_2-PadP44)") (class "Default")
      (node (ref "FPGA") (pin "P44") (pinfunction "IO_L62P_D5_2_P44") (pintype "passive"))
    )
    (net (code "102") (name "unconnected-(FPGA-IO_L63N_SCP6_0-PadP118)") (class "Default")
      (node (ref "FPGA") (pin "P118") (pinfunction "IO_L63N_SCP6_0_P118") (pintype "passive"))
    )
    (net (code "103") (name "unconnected-(FPGA-IO_L63P_SCP7_0-PadP119)") (class "Default")
      (node (ref "FPGA") (pin "P119") (pinfunction "IO_L63P_SCP7_0_P119") (pintype "passive"))
    )
    (net (code "104") (name "unconnected-(FPGA-IO_L64N_D9_2-PadP40)") (class "Default")
      (node (ref "FPGA") (pin "P40") (pinfunction "IO_L64N_D9_2_P40") (pintype "passive"))
    )
    (net (code "105") (name "unconnected-(FPGA-IO_L64N_SCP4_0-PadP116)") (class "Default")
      (node (ref "FPGA") (pin "P116") (pinfunction "IO_L64N_SCP4_0_P116") (pintype "passive"))
    )
    (net (code "106") (name "unconnected-(FPGA-IO_L64P_D8_2-PadP41)") (class "Default")
      (node (ref "FPGA") (pin "P41") (pinfunction "IO_L64P_D8_2_P41") (pintype "passive"))
    )
    (net (code "107") (name "unconnected-(FPGA-IO_L64P_SCP5_0-PadP117)") (class "Default")
      (node (ref "FPGA") (pin "P117") (pinfunction "IO_L64P_SCP5_0_P117") (pintype "passive"))
    )
    (net (code "108") (name "unconnected-(FPGA-IO_L65N_SCP2_0-PadP114)") (class "Default")
      (node (ref "FPGA") (pin "P114") (pinfunction "IO_L65N_SCP2_0_P114") (pintype "passive"))
    )
    (net (code "109") (name "unconnected-(FPGA-IO_L65P_SCP3_0-PadP115)") (class "Default")
      (node (ref "FPGA") (pin "P115") (pinfunction "IO_L65P_SCP3_0_P115") (pintype "passive"))
    )
    (net (code "110") (name "unconnected-(FPGA-IO_L66N_SCP0_0-PadP111)") (class "Default")
      (node (ref "FPGA") (pin "P111") (pinfunction "IO_L66N_SCP0_0_P111") (pintype "passive"))
    )
    (net (code "111") (name "unconnected-(FPGA-IO_L66N_SCP1_0-PadP112)") (class "Default")
      (node (ref "FPGA") (pin "P112") (pinfunction "IO_L66N_SCP1_0_P112") (pintype "passive"))
    )
    (net (code "112") (name "unconnected-(FPGA-IO_L74N_DOUT_BUSY_1-PadP74)") (class "Default")
      (node (ref "FPGA") (pin "P74") (pinfunction "IO_L74N_DOUT_BUSY_1_P74") (pintype "passive"))
    )
    (net (code "113") (name "unconnected-(FPGA-IO_L74P_AWAKE_1-PadP75)") (class "Default")
      (node (ref "FPGA") (pin "P75") (pinfunction "IO_L74P_AWAKE_1_P75") (pintype "passive"))
    )
    (net (code "114") (name "unconnected-(FPGA-IO_L83N_VREF_3-PadP1)") (class "Default")
      (node (ref "FPGA") (pin "P1") (pinfunction "IO_L83N_VREF_3_P1") (pintype "passive"))
    )
    (net (code "115") (name "unconnected-(FPGA-IO_L83P_3-PadP2)") (class "Default")
      (node (ref "FPGA") (pin "P2") (pinfunction "IO_L83P_3_P2") (pintype "passive"))
    )
  )
)
